# STB_TempControl.net
KiCad netlist of a schematic drawn in Altium Designer
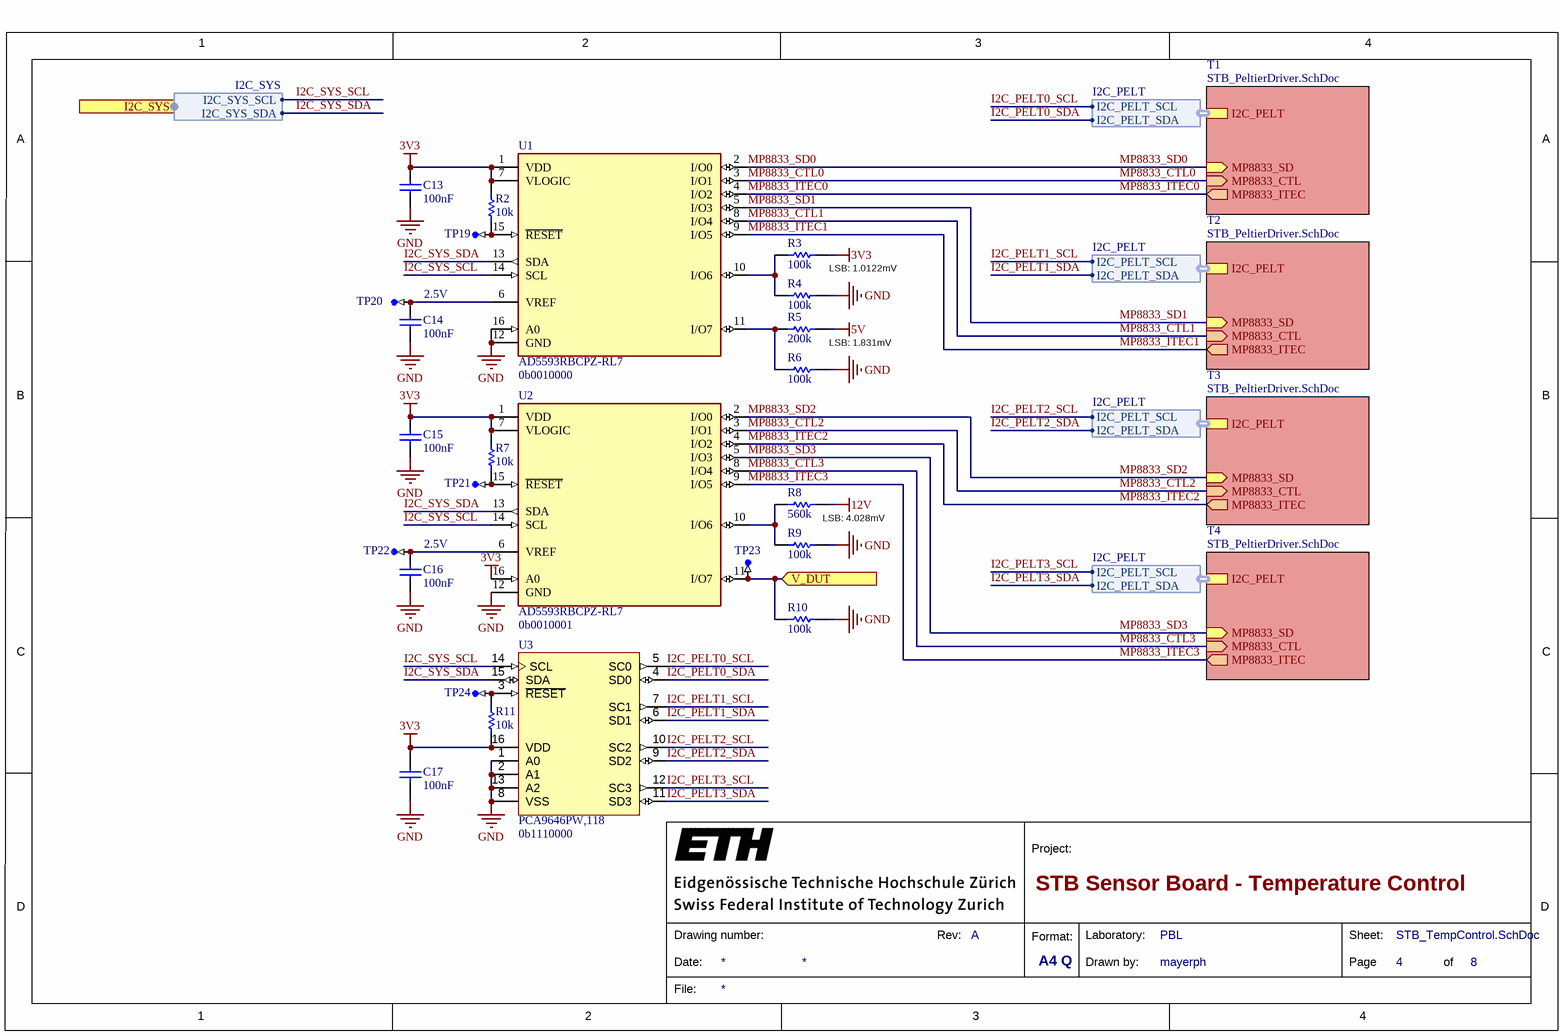
[diagram p0: STB_TempControl.SchDoc]

(export (version "E")
  (design (tool "Eeschema 10.0.6"))
  (components
    (comp (ref "C13")
      (value "100nF")
      (footprint "CAPC1050X55X23LL05T13")
      (description "Chip Capacitor, 100 nF, +/- 10%, 16 V, -55 to 125 degC, 0402 (1005 Metric), RoHS, Tape and Reel")
      (fields
        (field (name "MANUFACTURER") "Samsung Electro-Mechanics")
        (field (name "MANUFACTURER PART NUMBER") "CL05B104KO5NNNC")
      )
      (libsource (lib "Altium Content Vault") (part "CAP-NP-2"))
    )
    (comp (ref "C14")
      (value "100nF")
      (footprint "CAPC1050X55X23LL05T13")
      (description "Chip Capacitor, 100 nF, +/- 10%, 16 V, -55 to 125 degC, 0402 (1005 Metric), RoHS, Tape and Reel")
      (fields
        (field (name "MANUFACTURER") "Samsung Electro-Mechanics")
        (field (name "MANUFACTURER PART NUMBER") "CL05B104KO5NNNC")
      )
      (libsource (lib "Altium Content Vault") (part "CAP-NP-2"))
    )
    (comp (ref "C15")
      (value "100nF")
      (footprint "CAPC1050X55X23LL05T13")
      (description "Chip Capacitor, 100 nF, +/- 10%, 16 V, -55 to 125 degC, 0402 (1005 Metric), RoHS, Tape and Reel")
      (fields
        (field (name "MANUFACTURER") "Samsung Electro-Mechanics")
        (field (name "MANUFACTURER PART NUMBER") "CL05B104KO5NNNC")
      )
      (libsource (lib "Altium Content Vault") (part "CAP-NP-2"))
    )
    (comp (ref "C16")
      (value "100nF")
      (footprint "CAPC1050X55X23LL05T13")
      (description "Chip Capacitor, 100 nF, +/- 10%, 16 V, -55 to 125 degC, 0402 (1005 Metric), RoHS, Tape and Reel")
      (fields
        (field (name "MANUFACTURER") "Samsung Electro-Mechanics")
        (field (name "MANUFACTURER PART NUMBER") "CL05B104KO5NNNC")
      )
      (libsource (lib "Altium Content Vault") (part "CAP-NP-2"))
    )
    (comp (ref "C17")
      (value "100nF")
      (footprint "CAPC1050X55X23LL05T13")
      (description "Chip Capacitor, 100 nF, +/- 10%, 16 V, -55 to 125 degC, 0402 (1005 Metric), RoHS, Tape and Reel")
      (fields
        (field (name "MANUFACTURER") "Samsung Electro-Mechanics")
        (field (name "MANUFACTURER PART NUMBER") "CL05B104KO5NNNC")
      )
      (libsource (lib "Altium Content Vault") (part "CAP-NP-2"))
    )
    (comp (ref "R2")
      (value "10k")
      (footprint "RESC1005X40X25LL05T05")
      (description "Chip Resistor, 10 KOhm, +/- 1%, 0.1 W, -55 to 155 degC, 0402 (1005 Metric), RoHS, Tape and Reel")
      (fields (field (name "TOLERANCE") "1%") (field (name "MANUFACTURER") "Panasonic"))
      (libsource (lib "Altium Content Vault") (part "RES-2"))
    )
    (comp (ref "R3")
      (value "100k")
      (footprint "RESC1005X40X25LL05T10")
      (fields
        (field (name "PART NUMBER") "RC0402FR-07100KL")
        (field (name "MANUFACTURER") "Yageo / Phycomp")
        (field (name "TOLERANCE") "1%")
      )
      (libsource (lib "Altium Content Vault") (part "RES"))
    )
    (comp (ref "R4")
      (value "100k")
      (footprint "RESC1005X40X25LL05T10")
      (fields
        (field (name "PART NUMBER") "RC0402FR-07100KL")
        (field (name "MANUFACTURER") "Yageo / Phycomp")
        (field (name "TOLERANCE") "1%")
      )
      (libsource (lib "Altium Content Vault") (part "RES"))
    )
    (comp (ref "R5")
      (value "200k")
      (footprint "RESC1005X40X25LL05T10")
      (fields
        (field (name "PART NUMBER") "RC0402FR-07200KL")
        (field (name "MANUFACTURER") "Yageo / Phycomp")
        (field (name "TOLERANCE") "1%")
      )
      (libsource (lib "Altium Content Vault") (part "RES"))
    )
    (comp (ref "R6")
      (value "100k")
      (footprint "RESC1005X40X25LL05T10")
      (fields
        (field (name "PART NUMBER") "RC0402FR-07100KL")
        (field (name "MANUFACTURER") "Yageo / Phycomp")
        (field (name "TOLERANCE") "1%")
      )
      (libsource (lib "Altium Content Vault") (part "RES"))
    )
    (comp (ref "R7")
      (value "10k")
      (footprint "RESC1005X40X25LL05T05")
      (description "Chip Resistor, 10 KOhm, +/- 1%, 0.1 W, -55 to 155 degC, 0402 (1005 Metric), RoHS, Tape and Reel")
      (fields (field (name "TOLERANCE") "1%") (field (name "MANUFACTURER") "Panasonic"))
      (libsource (lib "Altium Content Vault") (part "RES-2"))
    )
    (comp (ref "R8")
      (value "560k")
      (footprint "RESC1005X40X25LL05T05")
      (fields
        (field (name "MANUFACTURER") "Panasonic")
        (field (name "PART NUMBER") "ERJ2RKF5603X")
        (field (name "MANUFACTURER PART NUMBER") "ERJ-2RKF5603X")
      )
      (libsource (lib "Altium Content Vault") (part "RES"))
    )
    (comp (ref "R9")
      (value "100k")
      (footprint "RESC1005X40X25LL05T10")
      (fields
        (field (name "PART NUMBER") "RC0402FR-07100KL")
        (field (name "MANUFACTURER") "Yageo / Phycomp")
        (field (name "TOLERANCE") "1%")
      )
      (libsource (lib "Altium Content Vault") (part "RES"))
    )
    (comp (ref "R10")
      (value "100k")
      (footprint "RESC1005X40X25LL05T10")
      (fields
        (field (name "PART NUMBER") "RC0402FR-07100KL")
        (field (name "MANUFACTURER") "Yageo / Phycomp")
        (field (name "TOLERANCE") "1%")
      )
      (libsource (lib "Altium Content Vault") (part "RES"))
    )
    (comp (ref "R11")
      (value "10k")
      (footprint "RESC1005X40X25LL05T05")
      (description "Chip Resistor, 10 KOhm, +/- 1%, 0.1 W, -55 to 155 degC, 0402 (1005 Metric), RoHS, Tape and Reel")
      (fields (field (name "TOLERANCE") "1%") (field (name "MANUFACTURER") "Panasonic"))
      (libsource (lib "Altium Content Vault") (part "RES-2"))
    )
    (comp (ref "TP19")
      (value "testPoint_1mm")
      (footprint "TP-SM-C-100")
      (description "testPoint 1mm")
      (libsource (lib "STB_Schlib") (part "testPoint_1mm"))
    )
    (comp (ref "TP20")
      (value "testPoint_1mm")
      (footprint "TP-SM-C-100")
      (description "testPoint 1mm")
      (libsource (lib "STB_Schlib") (part "testPoint_1mm"))
    )
    (comp (ref "TP21")
      (value "testPoint_1mm")
      (footprint "TP-SM-C-100")
      (description "testPoint 1mm")
      (libsource (lib "STB_Schlib") (part "testPoint_1mm"))
    )
    (comp (ref "TP22")
      (value "testPoint_1mm")
      (footprint "TP-SM-C-100")
      (description "testPoint 1mm")
      (libsource (lib "STB_Schlib") (part "testPoint_1mm"))
    )
    (comp (ref "TP23")
      (value "testPoint_1mm")
      (footprint "TP-SM-C-100")
      (description "testPoint 1mm")
      (libsource (lib "STB_Schlib") (part "testPoint_1mm"))
    )
    (comp (ref "TP24")
      (value "testPoint_1mm")
      (footprint "TP-SM-C-100")
      (description "testPoint 1mm")
      (libsource (lib "STB_Schlib") (part "testPoint_1mm"))
    )
    (comp (ref "U1")
      (value "AD5593RBCPZ-RL7")
      (footprint "FP-CP-16-32-IPC_C")
      (description "IC ADC/DAC 12BIT 16LFCSP")
      (fields (field (name "MANUFACTURER") "Analog Devices"))
      (libsource (lib "Altium Content Vault") (part "72185c2cc5c9389af25527886176d39"))
    )
    (comp (ref "U2")
      (value "AD5593RBCPZ-RL7")
      (footprint "FP-CP-16-32-IPC_C")
      (description "IC ADC/DAC 12BIT 16LFCSP")
      (fields (field (name "MANUFACTURER") "Analog Devices"))
      (libsource (lib "Altium Content Vault") (part "72185c2cc5c9389af25527886176d39"))
    )
    (comp (ref "U3")
      (value "PCA9646PW,118")
      (footprint "TSSOP-16_N")
      (description "Buffer, ReDriver 4 Channel 1MHz 16-TSSOP")
      (fields (field (name "MFR") "NXP USA Inc.") (field (name "MANUFACTURER") "NXP Semiconductors"))
      (libsource (lib "ETHZ Vault") (part "PCA9646PW,118"))
    )
  )
  (nets
    (net (code "3") (name "/I2C_PELT0_SCL") (class "Default")
      (node (ref "U3") (pin "5") (pinfunction "SC0_5") (pintype "output"))
    )
    (net (code "4") (name "/I2C_PELT0_SDA") (class "Default")
      (node (ref "U3") (pin "4") (pinfunction "SD0_4") (pintype "bidirectional"))
    )
    (net (code "5") (name "/I2C_PELT1_SCL") (class "Default")
      (node (ref "U3") (pin "7") (pinfunction "SC1_7") (pintype "output"))
    )
    (net (code "6") (name "/I2C_PELT1_SDA") (class "Default")
      (node (ref "U3") (pin "6") (pinfunction "SD1_6") (pintype "bidirectional"))
    )
    (net (code "7") (name "/I2C_PELT2_SCL") (class "Default")
      (node (ref "U3") (pin "10") (pinfunction "SC2_10") (pintype "output"))
    )
    (net (code "8") (name "/I2C_PELT2_SDA") (class "Default")
      (node (ref "U3") (pin "9") (pinfunction "SD2_9") (pintype "bidirectional"))
    )
    (net (code "9") (name "/I2C_PELT3_SCL") (class "Default")
      (node (ref "U3") (pin "12") (pinfunction "SC3_12") (pintype "output"))
    )
    (net (code "10") (name "/I2C_PELT3_SDA") (class "Default")
      (node (ref "U3") (pin "11") (pinfunction "SD3_11") (pintype "bidirectional"))
    )
    (net (code "11") (name "/I2C_SYS_SCL") (class "Default")
      (node (ref "U1") (pin "14") (pinfunction "SCL_14") (pintype "input"))
      (node (ref "U2") (pin "14") (pinfunction "SCL_14") (pintype "input"))
      (node (ref "U3") (pin "14") (pinfunction "SCL_14") (pintype "input"))
    )
    (net (code "12") (name "/I2C_SYS_SDA") (class "Default")
      (node (ref "U1") (pin "13") (pinfunction "SDA_13") (pintype "output"))
      (node (ref "U2") (pin "13") (pinfunction "SDA_13") (pintype "output"))
      (node (ref "U3") (pin "15") (pinfunction "SDA_15") (pintype "bidirectional"))
    )
    (net (code "13") (name "/MP8833_CTL0") (class "Default")
      (node (ref "U1") (pin "3") (pinfunction "I/O1_3") (pintype "bidirectional"))
    )
    (net (code "14") (name "/MP8833_CTL1") (class "Default")
      (node (ref "U1") (pin "8") (pinfunction "I/O4_8") (pintype "bidirectional"))
    )
    (net (code "15") (name "/MP8833_CTL2") (class "Default")
      (node (ref "U2") (pin "3") (pinfunction "I/O1_3") (pintype "bidirectional"))
    )
    (net (code "16") (name "/MP8833_CTL3") (class "Default")
      (node (ref "U2") (pin "8") (pinfunction "I/O4_8") (pintype "bidirectional"))
    )
    (net (code "17") (name "/MP8833_ITEC0") (class "Default")
      (node (ref "U1") (pin "4") (pinfunction "I/O2_4") (pintype "bidirectional"))
    )
    (net (code "18") (name "/MP8833_ITEC1") (class "Default")
      (node (ref "U1") (pin "9") (pinfunction "I/O5_9") (pintype "bidirectional"))
    )
    (net (code "19") (name "/MP8833_ITEC2") (class "Default")
      (node (ref "U2") (pin "4") (pinfunction "I/O2_4") (pintype "bidirectional"))
    )
    (net (code "20") (name "/MP8833_ITEC3") (class "Default")
      (node (ref "U2") (pin "9") (pinfunction "I/O5_9") (pintype "bidirectional"))
    )
    (net (code "21") (name "/MP8833_SD0") (class "Default")
      (node (ref "U1") (pin "2") (pinfunction "I/O0_2") (pintype "bidirectional"))
    )
    (net (code "22") (name "/MP8833_SD1") (class "Default")
      (node (ref "U1") (pin "5") (pinfunction "I/O3_5") (pintype "bidirectional"))
    )
    (net (code "23") (name "/MP8833_SD2") (class "Default")
      (node (ref "U2") (pin "2") (pinfunction "I/O0_2") (pintype "bidirectional"))
    )
    (net (code "24") (name "/MP8833_SD3") (class "Default")
      (node (ref "U2") (pin "5") (pinfunction "I/O3_5") (pintype "bidirectional"))
    )
    (net (code "25") (name "/V_DUT") (class "Default")
      (node (ref "R10") (pin "2") (pinfunction "2_2") (pintype "passive"))
      (node (ref "TP23") (pin "TP") (pinfunction "TP_TP") (pintype "input"))
      (node (ref "U2") (pin "11") (pinfunction "I/O7_11") (pintype "bidirectional"))
    )
    (net (code "28") (name "3V3") (class "Default")
      (node (ref "C13") (pin "2") (pinfunction "2_2") (pintype "passive"))
      (node (ref "C15") (pin "2") (pinfunction "2_2") (pintype "passive"))
      (node (ref "C17") (pin "2") (pinfunction "2_2") (pintype "passive"))
      (node (ref "R11") (pin "1") (pinfunction "1_1") (pintype "passive"))
      (node (ref "R2") (pin "2") (pinfunction "2_2") (pintype "passive"))
      (node (ref "R3") (pin "1") (pinfunction "1_1") (pintype "passive"))
      (node (ref "R7") (pin "2") (pinfunction "2_2") (pintype "passive"))
      (node (ref "U1") (pin "1") (pinfunction "VDD_1") (pintype "power_in"))
      (node (ref "U1") (pin "7") (pinfunction "VLOGIC_7") (pintype "power_in"))
      (node (ref "U2") (pin "1") (pinfunction "VDD_1") (pintype "power_in"))
      (node (ref "U2") (pin "16") (pinfunction "A0_16") (pintype "input"))
      (node (ref "U2") (pin "7") (pinfunction "VLOGIC_7") (pintype "power_in"))
      (node (ref "U3") (pin "16") (pinfunction "VDD_16") (pintype "power_in"))
    )
    (net (code "29") (name "5V") (class "Default")
      (node (ref "R5") (pin "1") (pinfunction "1_1") (pintype "passive"))
    )
    (net (code "30") (name "12V") (class "Default")
      (node (ref "R8") (pin "1") (pinfunction "1_1") (pintype "passive"))
    )
    (net (code "31") (name "GND") (class "Default")
      (node (ref "C13") (pin "1") (pinfunction "1_1") (pintype "passive"))
      (node (ref "C14") (pin "1") (pinfunction "1_1") (pintype "passive"))
      (node (ref "C15") (pin "1") (pinfunction "1_1") (pintype "passive"))
      (node (ref "C16") (pin "1") (pinfunction "1_1") (pintype "passive"))
      (node (ref "C17") (pin "1") (pinfunction "1_1") (pintype "passive"))
      (node (ref "R10") (pin "1") (pinfunction "1_1") (pintype "passive"))
      (node (ref "R4") (pin "1") (pinfunction "1_1") (pintype "passive"))
      (node (ref "R6") (pin "1") (pinfunction "1_1") (pintype "passive"))
      (node (ref "R9") (pin "1") (pinfunction "1_1") (pintype "passive"))
      (node (ref "U1") (pin "12") (pinfunction "GND_12") (pintype "power_in"))
      (node (ref "U1") (pin "16") (pinfunction "A0_16") (pintype "input"))
      (node (ref "U2") (pin "12") (pinfunction "GND_12") (pintype "power_in"))
      (node (ref "U3") (pin "1") (pinfunction "A0_1") (pintype "passive"))
      (node (ref "U3") (pin "13") (pinfunction "A2_13") (pintype "passive"))
      (node (ref "U3") (pin "2") (pinfunction "A1_2") (pintype "passive"))
      (node (ref "U3") (pin "8") (pinfunction "VSS_8") (pintype "power_in"))
    )
    (net (code "32") (name "Net-(U1-I{slash}O6)") (class "Default")
      (node (ref "R3") (pin "2") (pinfunction "2_2") (pintype "passive"))
      (node (ref "R4") (pin "2") (pinfunction "2_2") (pintype "passive"))
      (node (ref "U1") (pin "10") (pinfunction "I/O6_10") (pintype "bidirectional"))
    )
    (net (code "33") (name "Net-(U1-I{slash}O7)") (class "Default")
      (node (ref "R5") (pin "2") (pinfunction "2_2") (pintype "passive"))
      (node (ref "R6") (pin "2") (pinfunction "2_2") (pintype "passive"))
      (node (ref "U1") (pin "11") (pinfunction "I/O7_11") (pintype "bidirectional"))
    )
    (net (code "34") (name "Net-(U1-VREF)") (class "Default")
      (node (ref "C14") (pin "2") (pinfunction "2_2") (pintype "passive"))
      (node (ref "TP20") (pin "TP") (pinfunction "TP_TP") (pintype "input"))
      (node (ref "U1") (pin "6") (pinfunction "VREF_6") (pintype "power_in"))
    )
    (net (code "35") (name "Net-(U1-~{RESET})") (class "Default")
      (node (ref "R2") (pin "1") (pinfunction "1_1") (pintype "passive"))
      (node (ref "TP19") (pin "TP") (pinfunction "TP_TP") (pintype "input"))
      (node (ref "U1") (pin "15") (pinfunction "~{RESET}_15") (pintype "input"))
    )
    (net (code "36") (name "Net-(U2-I{slash}O6)") (class "Default")
      (node (ref "R8") (pin "2") (pinfunction "2_2") (pintype "passive"))
      (node (ref "R9") (pin "2") (pinfunction "2_2") (pintype "passive"))
      (node (ref "U2") (pin "10") (pinfunction "I/O6_10") (pintype "bidirectional"))
    )
    (net (code "37") (name "Net-(U2-VREF)") (class "Default")
      (node (ref "C16") (pin "2") (pinfunction "2_2") (pintype "passive"))
      (node (ref "TP22") (pin "TP") (pinfunction "TP_TP") (pintype "input"))
      (node (ref "U2") (pin "6") (pinfunction "VREF_6") (pintype "power_in"))
    )
    (net (code "38") (name "Net-(U2-~{RESET})") (class "Default")
      (node (ref "R7") (pin "1") (pinfunction "1_1") (pintype "passive"))
      (node (ref "TP21") (pin "TP") (pinfunction "TP_TP") (pintype "input"))
      (node (ref "U2") (pin "15") (pinfunction "~{RESET}_15") (pintype "input"))
    )
    (net (code "39") (name "Net-(U3-~{RESET})") (class "Default")
      (node (ref "R11") (pin "2") (pinfunction "2_2") (pintype "passive"))
      (node (ref "TP24") (pin "TP") (pinfunction "TP_TP") (pintype "input"))
      (node (ref "U3") (pin "3") (pinfunction "~{RESET}_3") (pintype "input"))
    )
  )
)
